# ECGSensor.net
KiCad netlist of a schematic drawn in EAGLE
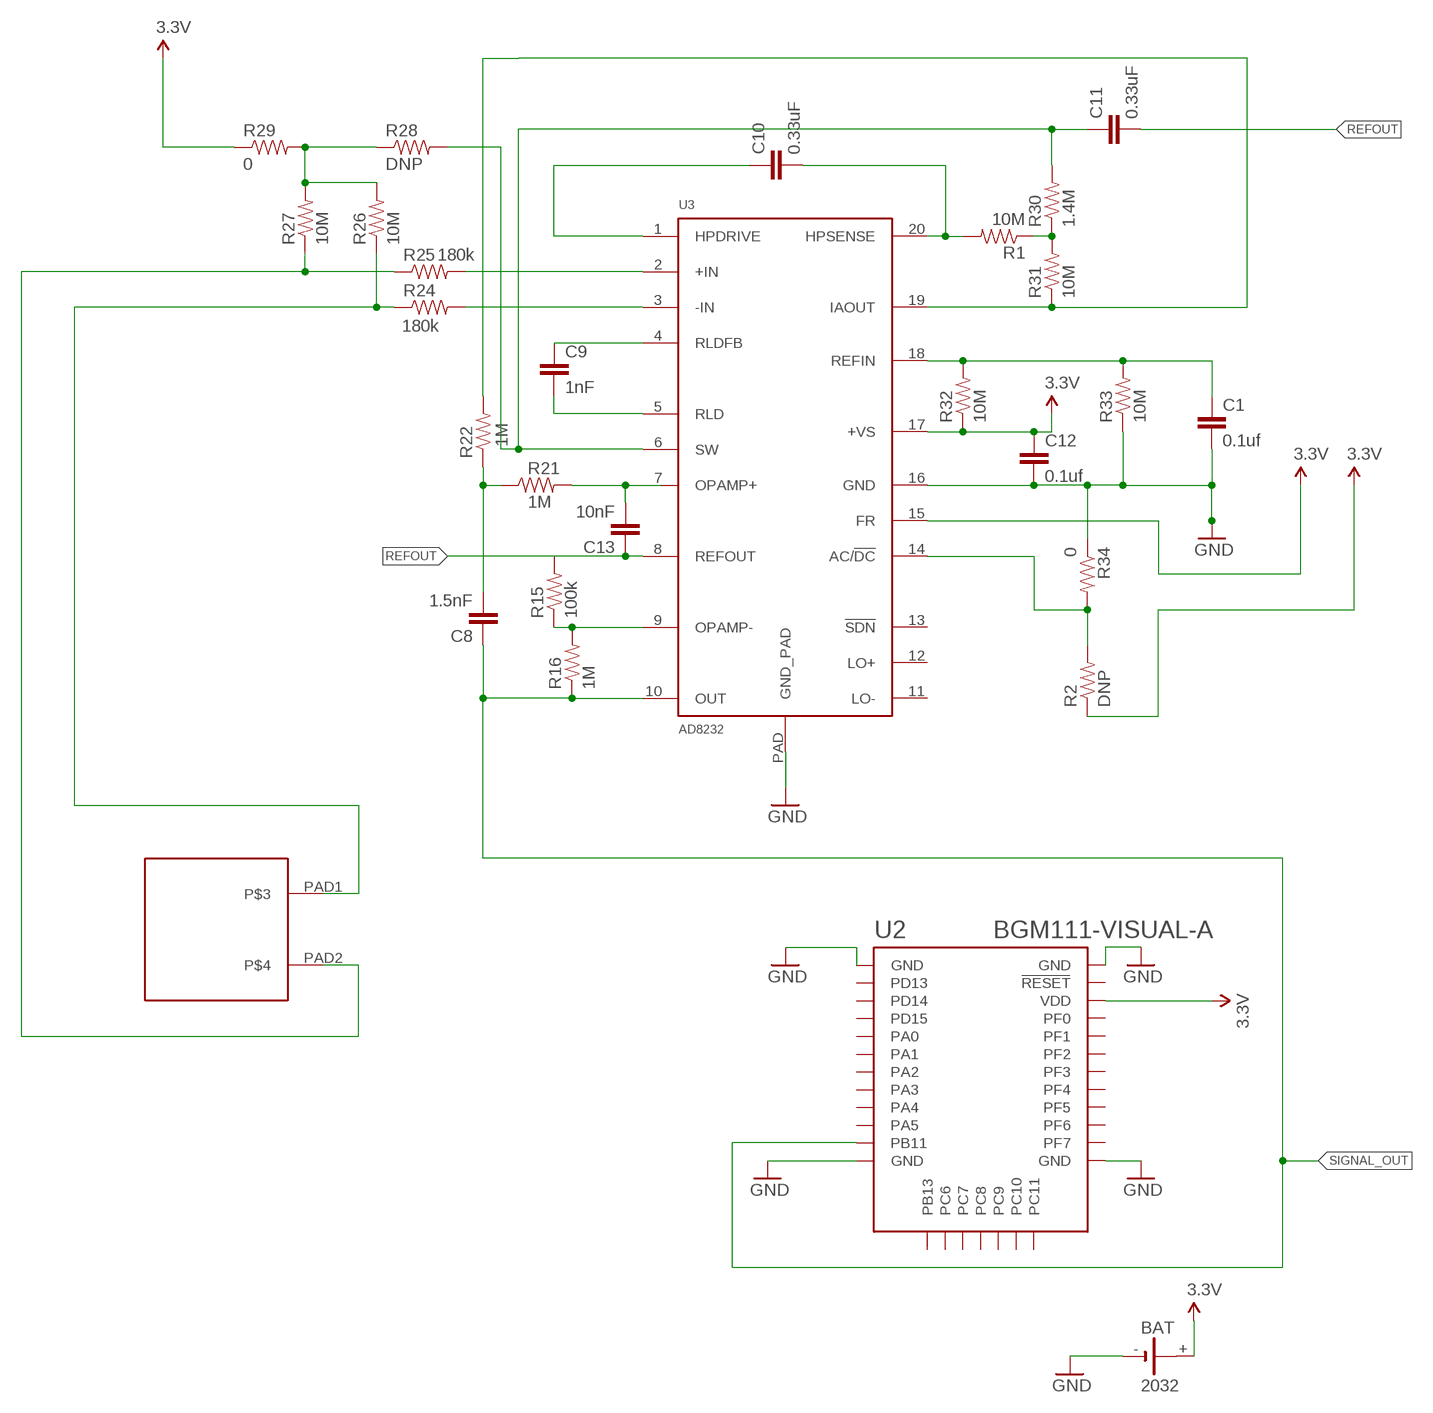
[diagram p0: schematic, sheet 1]

(export (version "E")
  (design (tool "Eeschema 10.0.6"))
  (components
    (comp (ref "BAT")
      (value "2032")
      (footprint "eagle-import:KZH20SMD")
      (libsource (lib "eagle-import") (part "2032"))
    )
    (comp (ref "C1")
      (value "0.1uf")
      (footprint "eagle-import:0603-CAP")
      (libsource (lib "eagle-import") (part "CAP0603-CAP"))
    )
    (comp (ref "C8")
      (value "1.5nF")
      (footprint "eagle-import:0603-CAP")
      (libsource (lib "eagle-import") (part "CAP0603-CAP"))
    )
    (comp (ref "C9")
      (value "1nF")
      (footprint "eagle-import:0603-CAP")
      (libsource (lib "eagle-import") (part "CAP0603-CAP"))
    )
    (comp (ref "C10")
      (value "0.33uF")
      (footprint "eagle-import:0805")
      (libsource (lib "eagle-import") (part "CAP0805"))
    )
    (comp (ref "C11")
      (value "0.33uF")
      (footprint "eagle-import:0805")
      (libsource (lib "eagle-import") (part "CAP0805"))
    )
    (comp (ref "C12")
      (value "0.1uf")
      (footprint "eagle-import:0603-CAP")
      (libsource (lib "eagle-import") (part "CAP0603-CAP"))
    )
    (comp (ref "C13")
      (value "10nF")
      (footprint "eagle-import:0603-CAP")
      (libsource (lib "eagle-import") (part "CAP0603-CAP"))
    )
    (comp (ref "R1")
      (value "10M")
      (footprint "eagle-import:0603-RES")
      (libsource (lib "eagle-import") (part "RESISTOR0603-RES"))
    )
    (comp (ref "R2")
      (value "DNP")
      (footprint "eagle-import:0603")
      (libsource (lib "eagle-import") (part "0OHM1/10W5%(0603)"))
    )
    (comp (ref "R15")
      (value "100k")
      (footprint "eagle-import:0603-RES")
      (libsource (lib "eagle-import") (part "RESISTOR0603-RES"))
    )
    (comp (ref "R16")
      (value "1M")
      (footprint "eagle-import:0603-RES")
      (libsource (lib "eagle-import") (part "RESISTOR0603-RES"))
    )
    (comp (ref "R21")
      (value "1M")
      (footprint "eagle-import:0603-RES")
      (libsource (lib "eagle-import") (part "RESISTOR0603-RES"))
    )
    (comp (ref "R22")
      (value "1M")
      (footprint "eagle-import:0603-RES")
      (libsource (lib "eagle-import") (part "RESISTOR0603-RES"))
    )
    (comp (ref "R24")
      (value "180k")
      (footprint "eagle-import:0603-RES")
      (libsource (lib "eagle-import") (part "RESISTOR0603-RES"))
    )
    (comp (ref "R25")
      (value "180k")
      (footprint "eagle-import:0603-RES")
      (libsource (lib "eagle-import") (part "RESISTOR0603-RES"))
    )
    (comp (ref "R26")
      (value "10M")
      (footprint "eagle-import:0603-RES")
      (libsource (lib "eagle-import") (part "RESISTOR0603-RES"))
    )
    (comp (ref "R27")
      (value "10M")
      (footprint "eagle-import:0603-RES")
      (libsource (lib "eagle-import") (part "RESISTOR0603-RES"))
    )
    (comp (ref "R28")
      (value "DNP")
      (footprint "eagle-import:0603")
      (libsource (lib "eagle-import") (part "0OHM1/10W5%(0603)"))
    )
    (comp (ref "R29")
      (value "0")
      (footprint "eagle-import:0603")
      (libsource (lib "eagle-import") (part "0OHM1/10W5%(0603)"))
    )
    (comp (ref "R30")
      (value "1.4M")
      (footprint "eagle-import:0603-RES")
      (libsource (lib "eagle-import") (part "RESISTOR0603-RES"))
    )
    (comp (ref "R31")
      (value "10M")
      (footprint "eagle-import:0603-RES")
      (libsource (lib "eagle-import") (part "RESISTOR0603-RES"))
    )
    (comp (ref "R32")
      (value "10M")
      (footprint "eagle-import:0603-RES")
      (libsource (lib "eagle-import") (part "RESISTOR0603-RES"))
    )
    (comp (ref "R33")
      (value "10M")
      (footprint "eagle-import:0603-RES")
      (libsource (lib "eagle-import") (part "RESISTOR0603-RES"))
    )
    (comp (ref "R34")
      (value "0")
      (footprint "eagle-import:0603")
      (libsource (lib "eagle-import") (part "0OHM1/10W5%(0603)"))
    )
    (comp (ref "U$1")
      (value "CPAD")
      (footprint "eagle-import:SNAPPAD")
      (libsource (lib "eagle-import") (part "CPAD"))
    )
    (comp (ref "U2")
      (value "BGM111-VISUAL-A")
      (footprint "eagle-import:BGM111-A")
      (libsource (lib "eagle-import") (part "BGM111-VISUAL-A"))
    )
    (comp (ref "U3")
      (value "AD8232")
      (footprint "eagle-import:LFCSP_20")
      (libsource (lib "eagle-import") (part "AD8232"))
    )
  )
  (nets
    (net (code "1") (name "3.3V") (class "Default")
      (node (ref "BAT") (pin "+") (pinfunction "+_+") (pintype "passive"))
      (node (ref "C12") (pin "1") (pinfunction "1_1") (pintype "passive"))
      (node (ref "R2") (pin "1") (pinfunction "1_1") (pintype "passive"))
      (node (ref "R29") (pin "1") (pinfunction "1_1") (pintype "passive"))
      (node (ref "R32") (pin "1") (pinfunction "1_1") (pintype "passive"))
      (node (ref "U2") (pin "VDD") (pinfunction "VDD_VDD") (pintype "power_in"))
      (node (ref "U3") (pin "15") (pinfunction "FR_15") (pintype "bidirectional"))
      (node (ref "U3") (pin "17") (pinfunction "+VS_17") (pintype "bidirectional"))
    )
    (net (code "2") (name "GND") (class "Default")
      (node (ref "BAT") (pin "-") (pinfunction "-_-") (pintype "passive"))
      (node (ref "C1") (pin "2") (pinfunction "2_2") (pintype "passive"))
      (node (ref "C12") (pin "2") (pinfunction "2_2") (pintype "passive"))
      (node (ref "R33") (pin "1") (pinfunction "1_1") (pintype "passive"))
      (node (ref "R34") (pin "1") (pinfunction "1_1") (pintype "passive"))
      (node (ref "U2") (pin "GND") (pinfunction "GND_GND") (pintype "power_in"))
      (node (ref "U2") (pin "GND@2") (pinfunction "GND_GND@2") (pintype "power_in"))
      (node (ref "U2") (pin "GND@3") (pinfunction "GND_GND@3") (pintype "power_in"))
      (node (ref "U2") (pin "GND@4") (pinfunction "GND_GND@4") (pintype "power_in"))
      (node (ref "U3") (pin "16") (pinfunction "GND_16") (pintype "bidirectional"))
      (node (ref "U3") (pin "PAD") (pinfunction "GND_PAD_PAD") (pintype "bidirectional"))
    )
    (net (code "3") (name "Net-(C8-Pad2)") (class "Default")
      (node (ref "C8") (pin "2") (pinfunction "2_2") (pintype "passive"))
      (node (ref "R21") (pin "1") (pinfunction "1_1") (pintype "passive"))
      (node (ref "R22") (pin "1") (pinfunction "1_1") (pintype "passive"))
    )
    (net (code "4") (name "Net-(C13-Pad2)") (class "Default")
      (node (ref "C13") (pin "2") (pinfunction "2_2") (pintype "passive"))
      (node (ref "R21") (pin "2") (pinfunction "2_2") (pintype "passive"))
    )
    (net (code "5") (name "Net-(R1-Pad1)") (class "Default")
      (node (ref "R1") (pin "1") (pinfunction "1_1") (pintype "passive"))
      (node (ref "R30") (pin "1") (pinfunction "1_1") (pintype "passive"))
      (node (ref "R31") (pin "2") (pinfunction "2_2") (pintype "passive"))
    )
    (net (code "6") (name "Net-(R25-Pad1)") (class "Default")
      (node (ref "R25") (pin "1") (pinfunction "1_1") (pintype "passive"))
      (node (ref "R27") (pin "1") (pinfunction "1_1") (pintype "passive"))
    )
    (net (code "7") (name "Net-(R26-Pad2)") (class "Default")
      (node (ref "R26") (pin "2") (pinfunction "2_2") (pintype "passive"))
      (node (ref "R27") (pin "2") (pinfunction "2_2") (pintype "passive"))
      (node (ref "R28") (pin "1") (pinfunction "1_1") (pintype "passive"))
      (node (ref "R29") (pin "2") (pinfunction "2_2") (pintype "passive"))
    )
    (net (code "8") (name "Net-(U$1-P$3)") (class "Default")
      (node (ref "R24") (pin "1") (pinfunction "1_1") (pintype "passive"))
      (node (ref "R26") (pin "1") (pinfunction "1_1") (pintype "passive"))
      (node (ref "U$1") (pin "PAD1") (pinfunction "P$3_PAD1") (pintype "bidirectional"))
    )
    (net (code "9") (name "Net-(U3-+IN)") (class "Default")
      (node (ref "R25") (pin "2") (pinfunction "2_2") (pintype "passive"))
      (node (ref "U3") (pin "2") (pinfunction "+IN_2") (pintype "bidirectional"))
    )
    (net (code "10") (name "Net-(U3--IN)") (class "Default")
      (node (ref "R24") (pin "2") (pinfunction "2_2") (pintype "passive"))
      (node (ref "U3") (pin "3") (pinfunction "-IN_3") (pintype "bidirectional"))
    )
    (net (code "11") (name "Net-(U3-AC{slash}~{DC})") (class "Default")
      (node (ref "R2") (pin "2") (pinfunction "2_2") (pintype "passive"))
      (node (ref "R34") (pin "2") (pinfunction "2_2") (pintype "passive"))
      (node (ref "U3") (pin "14") (pinfunction "AC/~{DC}_14") (pintype "bidirectional"))
    )
    (net (code "12") (name "Net-(U3-HPDRIVE)") (class "Default")
      (node (ref "C10") (pin "1") (pinfunction "1_1") (pintype "passive"))
      (node (ref "U3") (pin "1") (pinfunction "HPDRIVE_1") (pintype "bidirectional"))
    )
    (net (code "13") (name "Net-(U3-HPSENSE)") (class "Default")
      (node (ref "C10") (pin "2") (pinfunction "2_2") (pintype "passive"))
      (node (ref "R1") (pin "2") (pinfunction "2_2") (pintype "passive"))
      (node (ref "U3") (pin "20") (pinfunction "HPSENSE_20") (pintype "bidirectional"))
    )
    (net (code "14") (name "Net-(U3-IAOUT)") (class "Default")
      (node (ref "R22") (pin "2") (pinfunction "2_2") (pintype "passive"))
      (node (ref "R31") (pin "1") (pinfunction "1_1") (pintype "passive"))
      (node (ref "U3") (pin "19") (pinfunction "IAOUT_19") (pintype "bidirectional"))
    )
    (net (code "15") (name "Net-(U3-OPAMP-)") (class "Default")
      (node (ref "R15") (pin "1") (pinfunction "1_1") (pintype "passive"))
      (node (ref "R16") (pin "2") (pinfunction "2_2") (pintype "passive"))
      (node (ref "U3") (pin "9") (pinfunction "OPAMP-_9") (pintype "bidirectional"))
    )
    (net (code "16") (name "Net-(U3-REFIN)") (class "Default")
      (node (ref "C1") (pin "1") (pinfunction "1_1") (pintype "passive"))
      (node (ref "R32") (pin "2") (pinfunction "2_2") (pintype "passive"))
      (node (ref "R33") (pin "2") (pinfunction "2_2") (pintype "passive"))
      (node (ref "U3") (pin "18") (pinfunction "REFIN_18") (pintype "bidirectional"))
    )
    (net (code "17") (name "Net-(U3-REFOUT)") (class "Default")
      (node (ref "C13") (pin "1") (pinfunction "1_1") (pintype "passive"))
      (node (ref "R15") (pin "2") (pinfunction "2_2") (pintype "passive"))
      (node (ref "U3") (pin "8") (pinfunction "REFOUT_8") (pintype "bidirectional"))
    )
    (net (code "18") (name "Net-(U3-RLD)") (class "Default")
      (node (ref "C9") (pin "2") (pinfunction "2_2") (pintype "passive"))
      (node (ref "U3") (pin "5") (pinfunction "RLD_5") (pintype "bidirectional"))
    )
    (net (code "19") (name "Net-(U3-RLDFB)") (class "Default")
      (node (ref "C9") (pin "1") (pinfunction "1_1") (pintype "passive"))
      (node (ref "U3") (pin "4") (pinfunction "RLDFB_4") (pintype "bidirectional"))
    )
    (net (code "20") (name "Net-(U3-SW)") (class "Default")
      (node (ref "C11") (pin "1") (pinfunction "1_1") (pintype "passive"))
      (node (ref "R28") (pin "2") (pinfunction "2_2") (pintype "passive"))
      (node (ref "R30") (pin "2") (pinfunction "2_2") (pintype "passive"))
      (node (ref "U3") (pin "6") (pinfunction "SW_6") (pintype "bidirectional"))
    )
    (net (code "22") (name "SIGNAL_OUT") (class "Default")
      (node (ref "C8") (pin "1") (pinfunction "1_1") (pintype "passive"))
      (node (ref "R16") (pin "1") (pinfunction "1_1") (pintype "passive"))
      (node (ref "U2") (pin "PB11") (pinfunction "PB11_PB11") (pintype "bidirectional"))
      (node (ref "U3") (pin "10") (pinfunction "OUT_10") (pintype "bidirectional"))
    )
    (net (code "23") (name "unconnected-(C11-Pad2)") (class "Default")
      (node (ref "C11") (pin "2") (pinfunction "2_2") (pintype "passive"))
    )
    (net (code "24") (name "unconnected-(U$1-P$4-PadPAD2)") (class "Default")
      (node (ref "U$1") (pin "PAD2") (pinfunction "P$4_PAD2") (pintype "bidirectional"))
    )
    (net (code "25") (name "unconnected-(U2-PadPA0)") (class "Default")
      (node (ref "U2") (pin "PA0") (pinfunction "PA0_PA0") (pintype "bidirectional"))
    )
    (net (code "26") (name "unconnected-(U2-PadPA1)") (class "Default")
      (node (ref "U2") (pin "PA1") (pinfunction "PA1_PA1") (pintype "bidirectional"))
    )
    (net (code "27") (name "unconnected-(U2-PadPA2)") (class "Default")
      (node (ref "U2") (pin "PA2") (pinfunction "PA2_PA2") (pintype "bidirectional"))
    )
    (net (code "28") (name "unconnected-(U2-PadPA3)") (class "Default")
      (node (ref "U2") (pin "PA3") (pinfunction "PA3_PA3") (pintype "bidirectional"))
    )
    (net (code "29") (name "unconnected-(U2-PadPA4)") (class "Default")
      (node (ref "U2") (pin "PA4") (pinfunction "PA4_PA4") (pintype "bidirectional"))
    )
    (net (code "30") (name "unconnected-(U2-PadPA5)") (class "Default")
      (node (ref "U2") (pin "PA5") (pinfunction "PA5_PA5") (pintype "bidirectional"))
    )
    (net (code "31") (name "unconnected-(U2-PadPB13)") (class "Default")
      (node (ref "U2") (pin "PB13") (pinfunction "PB13_PB13") (pintype "bidirectional"))
    )
    (net (code "32") (name "unconnected-(U2-PadPC6)") (class "Default")
      (node (ref "U2") (pin "PC6") (pinfunction "PC6_PC6") (pintype "bidirectional"))
    )
    (net (code "33") (name "unconnected-(U2-PadPC7)") (class "Default")
      (node (ref "U2") (pin "PC7") (pinfunction "PC7_PC7") (pintype "bidirectional"))
    )
    (net (code "34") (name "unconnected-(U2-PadPC8)") (class "Default")
      (node (ref "U2") (pin "PC8") (pinfunction "PC8_PC8") (pintype "bidirectional"))
    )
    (net (code "35") (name "unconnected-(U2-PadPC9)") (class "Default")
      (node (ref "U2") (pin "PC9") (pinfunction "PC9_PC9") (pintype "bidirectional"))
    )
    (net (code "36") (name "unconnected-(U2-PadPC10)") (class "Default")
      (node (ref "U2") (pin "PC10") (pinfunction "PC10_PC10") (pintype "bidirectional"))
    )
    (net (code "37") (name "unconnected-(U2-PadPC11)") (class "Default")
      (node (ref "U2") (pin "PC11") (pinfunction "PC11_PC11") (pintype "bidirectional"))
    )
    (net (code "38") (name "unconnected-(U2-PadPD13)") (class "Default")
      (node (ref "U2") (pin "PD13") (pinfunction "PD13_PD13") (pintype "bidirectional"))
    )
    (net (code "39") (name "unconnected-(U2-PadPD14)") (class "Default")
      (node (ref "U2") (pin "PD14") (pinfunction "PD14_PD14") (pintype "bidirectional"))
    )
    (net (code "40") (name "unconnected-(U2-PadPD15)") (class "Default")
      (node (ref "U2") (pin "PD15") (pinfunction "PD15_PD15") (pintype "bidirectional"))
    )
    (net (code "41") (name "unconnected-(U2-PadPF0)") (class "Default")
      (node (ref "U2") (pin "PF0") (pinfunction "PF0_PF0") (pintype "bidirectional"))
    )
    (net (code "42") (name "unconnected-(U2-PadPF1)") (class "Default")
      (node (ref "U2") (pin "PF1") (pinfunction "PF1_PF1") (pintype "bidirectional"))
    )
    (net (code "43") (name "unconnected-(U2-PadPF2)") (class "Default")
      (node (ref "U2") (pin "PF2") (pinfunction "PF2_PF2") (pintype "bidirectional"))
    )
    (net (code "44") (name "unconnected-(U2-PadPF3)") (class "Default")
      (node (ref "U2") (pin "PF3") (pinfunction "PF3_PF3") (pintype "bidirectional"))
    )
    (net (code "45") (name "unconnected-(U2-PadPF4)") (class "Default")
      (node (ref "U2") (pin "PF4") (pinfunction "PF4_PF4") (pintype "bidirectional"))
    )
    (net (code "46") (name "unconnected-(U2-PadPF5)") (class "Default")
      (node (ref "U2") (pin "PF5") (pinfunction "PF5_PF5") (pintype "bidirectional"))
    )
    (net (code "47") (name "unconnected-(U2-PadPF6)") (class "Default")
      (node (ref "U2") (pin "PF6") (pinfunction "PF6_PF6") (pintype "bidirectional"))
    )
    (net (code "48") (name "unconnected-(U2-PadPF7)") (class "Default")
      (node (ref "U2") (pin "PF7") (pinfunction "PF7_PF7") (pintype "bidirectional"))
    )
    (net (code "49") (name "unconnected-(U2-PadRESET)") (class "Default")
      (node (ref "U2") (pin "RESET") (pinfunction "RESET_RESET") (pintype "input"))
    )
    (net (code "50") (name "unconnected-(U3-LO+-Pad12)") (class "Default")
      (node (ref "U3") (pin "12") (pinfunction "LO+_12") (pintype "bidirectional"))
    )
    (net (code "51") (name "unconnected-(U3-LO--Pad11)") (class "Default")
      (node (ref "U3") (pin "11") (pinfunction "LO-_11") (pintype "bidirectional"))
    )
    (net (code "52") (name "unconnected-(U3-OPAMP+-Pad7)") (class "Default")
      (node (ref "U3") (pin "7") (pinfunction "OPAMP+_7") (pintype "bidirectional"))
    )
    (net (code "53") (name "unconnected-(U3-~{SDN}-Pad13)") (class "Default")
      (node (ref "U3") (pin "13") (pinfunction "~{SDN}_13") (pintype "bidirectional"))
    )
  )
)
